# lcd.net
KiCad netlist of a schematic drawn in Altium Designer
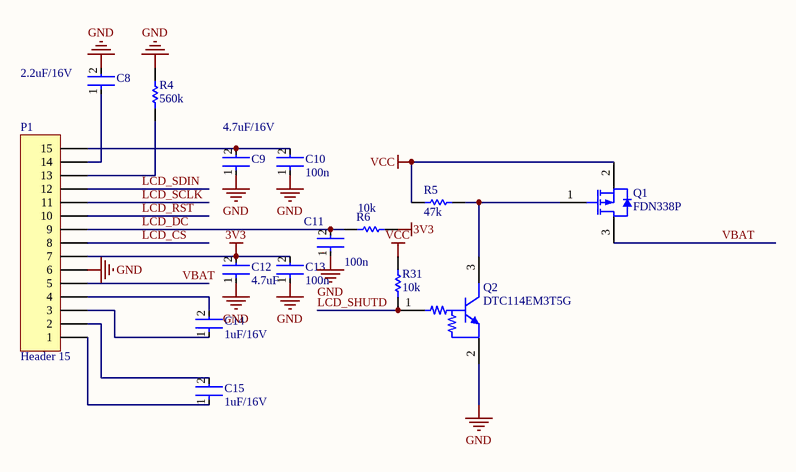
[diagram p0: lcd.SchDoc]

(export (version "E")
  (design (tool "Eeschema 10.0.6"))
  (components
    (comp (ref "C8")
      (value "2.2uF/16V")
      (footprint "FP-GRM188-0_1-e0_2_0_55-IPC_A")
      (description "Chip Multilayer Ceramic Capacitors for General Purpose, 0603, 10uF, X5R, 15%, 20%, 6.3V")
      (fields (field (name "VOLTAGE") "6.3V") (field (name "TOLERANCE") "20%"))
      (libsource (lib "Altium Content Vault") (part "02cd4be3c70576c341d710602a673aa"))
    )
    (comp (ref "C9")
      (value "4.7uF/16V")
      (footprint "FP-GRM188-0_1-e0_2_0_55-IPC_A")
      (description "Chip Multilayer Ceramic Capacitors for General Purpose, 0603, 10uF, X5R, 15%, 20%, 6.3V")
      (fields (field (name "VOLTAGE") "6.3V") (field (name "TOLERANCE") "20%"))
      (libsource (lib "Altium Content Vault") (part "02cd4be3c70576c341d710602a673aa"))
    )
    (comp (ref "C10")
      (value "100n")
      (footprint "FP-GRM155-0_05-IPC_A")
      (description "Chip Multilayer Ceramic Capacitors for General Purpose, 0402, 470pF, C0G, 30ppm/°C, 5%, 50V")
      (fields (field (name "VOLTAGE") "50V") (field (name "TOLERANCE") "5%"))
      (libsource (lib "Altium Content Vault") (part "02cd4be3c70576c341d710602a673aa"))
    )
    (comp (ref "C11")
      (value "100n")
      (footprint "FP-GRM155-0_05-IPC_A")
      (description "Chip Multilayer Ceramic Capacitors for General Purpose, 0402, 470pF, C0G, 30ppm/°C, 5%, 50V")
      (fields (field (name "VOLTAGE") "50V") (field (name "TOLERANCE") "5%"))
      (libsource (lib "Altium Content Vault") (part "02cd4be3c70576c341d710602a673aa"))
    )
    (comp (ref "C12")
      (value "4.7uF")
      (footprint "FP-GRM188-0_1-e0_2_0_55-IPC_A")
      (description "Chip Multilayer Ceramic Capacitors for General Purpose, 0603, 10uF, X5R, 15%, 20%, 6.3V")
      (fields (field (name "VOLTAGE") "6.3V") (field (name "TOLERANCE") "20%"))
      (libsource (lib "Altium Content Vault") (part "02cd4be3c70576c341d710602a673aa"))
    )
    (comp (ref "C13")
      (value "100n")
      (footprint "FP-GRM155-0_05-IPC_A")
      (description "Chip Multilayer Ceramic Capacitors for General Purpose, 0402, 470pF, C0G, 30ppm/°C, 5%, 50V")
      (fields (field (name "VOLTAGE") "50V") (field (name "TOLERANCE") "5%"))
      (libsource (lib "Altium Content Vault") (part "02cd4be3c70576c341d710602a673aa"))
    )
    (comp (ref "C14")
      (value "1uF/16V")
      (footprint "FP-GRM188-0_1-e0_2_0_55-IPC_A")
      (description "Chip Multilayer Ceramic Capacitors for General Purpose, 0603, 10uF, X5R, 15%, 20%, 6.3V")
      (fields (field (name "VOLTAGE") "6.3V") (field (name "TOLERANCE") "20%"))
      (libsource (lib "Altium Content Vault") (part "02cd4be3c70576c341d710602a673aa"))
    )
    (comp (ref "C15")
      (value "1uF/16V")
      (footprint "FP-GRM188-0_1-e0_2_0_55-IPC_A")
      (description "Chip Multilayer Ceramic Capacitors for General Purpose, 0603, 10uF, X5R, 15%, 20%, 6.3V")
      (fields (field (name "VOLTAGE") "6.3V") (field (name "TOLERANCE") "20%"))
      (libsource (lib "Altium Content Vault") (part "02cd4be3c70576c341d710602a673aa"))
    )
    (comp (ref "P1")
      (value "Header 15")
      (footprint "FLEX_CONN")
      (description "Header, 15-Pin")
      (fields (field (name "PUBLISHER") "Altium Limited"))
      (libsource (lib "Miscellaneous Connectors") (part "Header 15"))
    )
    (comp (ref "Q1")
      (value "FDN338P")
      (footprint "FAIR-SSOT3L-3_V")
      (fields (field (name "MANUFACTURER") "Fairchild Semiconductor"))
      (libsource (lib "Altium Content Vault") (part "PEMOS-GSD-3"))
    )
    (comp (ref "Q2")
      (value "DTC114EM3T5G")
      (footprint "ONSC-SOT-723-3-631AA-01_V")
      (fields (field (name "MANUFACTURER") "On Semiconductor"))
      (libsource (lib "Altium Content Vault") (part "ONSC-BRT-NPN-B1E2C3-3"))
    )
    (comp (ref "R4")
      (value "560k")
      (footprint "RESC1005X40X25NL05T10")
      (fields (field (name "MANUFACTURER") "Yageo / Phycomp") (field (name "PART NUMBER") "RC0402JR-070RL"))
      (libsource (lib "Altium Content Vault") (part "RES"))
    )
    (comp (ref "R5")
      (value "47k")
      (footprint "RESC1005X40X25NL05T10")
      (fields (field (name "MANUFACTURER") "Yageo / Phycomp") (field (name "PART NUMBER") "RC0402JR-070RL"))
      (libsource (lib "Altium Content Vault") (part "RES"))
    )
    (comp (ref "R6")
      (value "10k")
      (footprint "RESC1005X40X25NL05T10")
      (fields (field (name "MANUFACTURER") "Yageo / Phycomp") (field (name "PART NUMBER") "RC0402JR-070RL"))
      (libsource (lib "Altium Content Vault") (part "RES"))
    )
    (comp (ref "R31")
      (value "10k")
      (footprint "RESC1005X40X25NL05T10")
      (fields (field (name "MANUFACTURER") "Yageo / Phycomp") (field (name "PART NUMBER") "RC0402JR-070RL"))
      (libsource (lib "Altium Content Vault") (part "RES"))
    )
  )
  (nets
    (net (code "1") (name "/LCD_CS") (class "Default")
      (node (ref "P1") (pin "8") (pinfunction "8_8") (pintype "passive"))
    )
    (net (code "2") (name "/LCD_DC") (class "Default")
      (node (ref "C11") (pin "2") (pinfunction "2_2") (pintype "passive"))
      (node (ref "P1") (pin "9") (pinfunction "9_9") (pintype "passive"))
      (node (ref "R6") (pin "2") (pinfunction "2_2") (pintype "passive"))
    )
    (net (code "3") (name "/LCD_RST") (class "Default")
      (node (ref "P1") (pin "10") (pinfunction "10_10") (pintype "passive"))
    )
    (net (code "4") (name "/LCD_SCLK") (class "Default")
      (node (ref "P1") (pin "11") (pinfunction "11_11") (pintype "passive"))
    )
    (net (code "5") (name "/LCD_SDIN") (class "Default")
      (node (ref "P1") (pin "12") (pinfunction "12_12") (pintype "passive"))
    )
    (net (code "6") (name "/LCD_SHUTD") (class "Default")
      (node (ref "Q2") (pin "1") (pinfunction "B_1") (pintype "passive"))
      (node (ref "R31") (pin "1") (pinfunction "1_1") (pintype "passive"))
    )
    (net (code "7") (name "/VBAT") (class "Default")
      (node (ref "P1") (pin "5") (pinfunction "5_5") (pintype "passive"))
      (node (ref "Q1") (pin "3") (pinfunction "DRAIN_3") (pintype "passive"))
    )
    (net (code "8") (name "3V3") (class "Default")
      (node (ref "C12") (pin "2") (pinfunction "2_2") (pintype "passive"))
      (node (ref "C13") (pin "2") (pinfunction "2_2") (pintype "passive"))
      (node (ref "P1") (pin "7") (pinfunction "7_7") (pintype "passive"))
      (node (ref "R6") (pin "1") (pinfunction "1_1") (pintype "passive"))
    )
    (net (code "9") (name "GND") (class "Default")
      (node (ref "C10") (pin "1") (pinfunction "1_1") (pintype "passive"))
      (node (ref "C11") (pin "1") (pinfunction "1_1") (pintype "passive"))
      (node (ref "C12") (pin "1") (pinfunction "1_1") (pintype "passive"))
      (node (ref "C13") (pin "1") (pinfunction "1_1") (pintype "passive"))
      (node (ref "C8") (pin "2") (pinfunction "2_2") (pintype "passive"))
      (node (ref "C9") (pin "1") (pinfunction "1_1") (pintype "passive"))
      (node (ref "P1") (pin "6") (pinfunction "6_6") (pintype "passive"))
      (node (ref "Q2") (pin "2") (pinfunction "E_2") (pintype "passive"))
      (node (ref "R4") (pin "2") (pinfunction "2_2") (pintype "passive"))
    )
    (net (code "10") (name "Net-(C8-Pad1)") (class "Default")
      (node (ref "C8") (pin "1") (pinfunction "1_1") (pintype "passive"))
      (node (ref "P1") (pin "14") (pinfunction "14_14") (pintype "passive"))
    )
    (net (code "11") (name "Net-(C10-Pad2)") (class "Default")
      (node (ref "C10") (pin "2") (pinfunction "2_2") (pintype "passive"))
      (node (ref "C9") (pin "2") (pinfunction "2_2") (pintype "passive"))
      (node (ref "P1") (pin "15") (pinfunction "15_15") (pintype "passive"))
    )
    (net (code "12") (name "Net-(C14-Pad1)") (class "Default")
      (node (ref "C14") (pin "1") (pinfunction "1_1") (pintype "passive"))
      (node (ref "P1") (pin "3") (pinfunction "3_3") (pintype "passive"))
    )
    (net (code "13") (name "Net-(C14-Pad2)") (class "Default")
      (node (ref "C14") (pin "2") (pinfunction "2_2") (pintype "passive"))
      (node (ref "P1") (pin "4") (pinfunction "4_4") (pintype "passive"))
    )
    (net (code "14") (name "Net-(C15-Pad1)") (class "Default")
      (node (ref "C15") (pin "1") (pinfunction "1_1") (pintype "passive"))
      (node (ref "P1") (pin "1") (pinfunction "1_1") (pintype "passive"))
    )
    (net (code "15") (name "Net-(C15-Pad2)") (class "Default")
      (node (ref "C15") (pin "2") (pinfunction "2_2") (pintype "passive"))
      (node (ref "P1") (pin "2") (pinfunction "2_2") (pintype "passive"))
    )
    (net (code "16") (name "Net-(P1-Pad13)") (class "Default")
      (node (ref "P1") (pin "13") (pinfunction "13_13") (pintype "passive"))
      (node (ref "R4") (pin "1") (pinfunction "1_1") (pintype "passive"))
    )
    (net (code "17") (name "Net-(Q1-GATE)") (class "Default")
      (node (ref "Q1") (pin "1") (pinfunction "GATE_1") (pintype "passive"))
      (node (ref "Q2") (pin "3") (pinfunction "C_3") (pintype "passive"))
      (node (ref "R5") (pin "2") (pinfunction "2_2") (pintype "passive"))
    )
    (net (code "18") (name "VCC") (class "Default")
      (node (ref "Q1") (pin "2") (pinfunction "SOURCE_2") (pintype "passive"))
      (node (ref "R31") (pin "2") (pinfunction "2_2") (pintype "passive"))
      (node (ref "R5") (pin "1") (pinfunction "1_1") (pintype "passive"))
    )
  )
)
